# PROK_drum_F.net
KiCad netlist of a schematic drawn in EAGLE
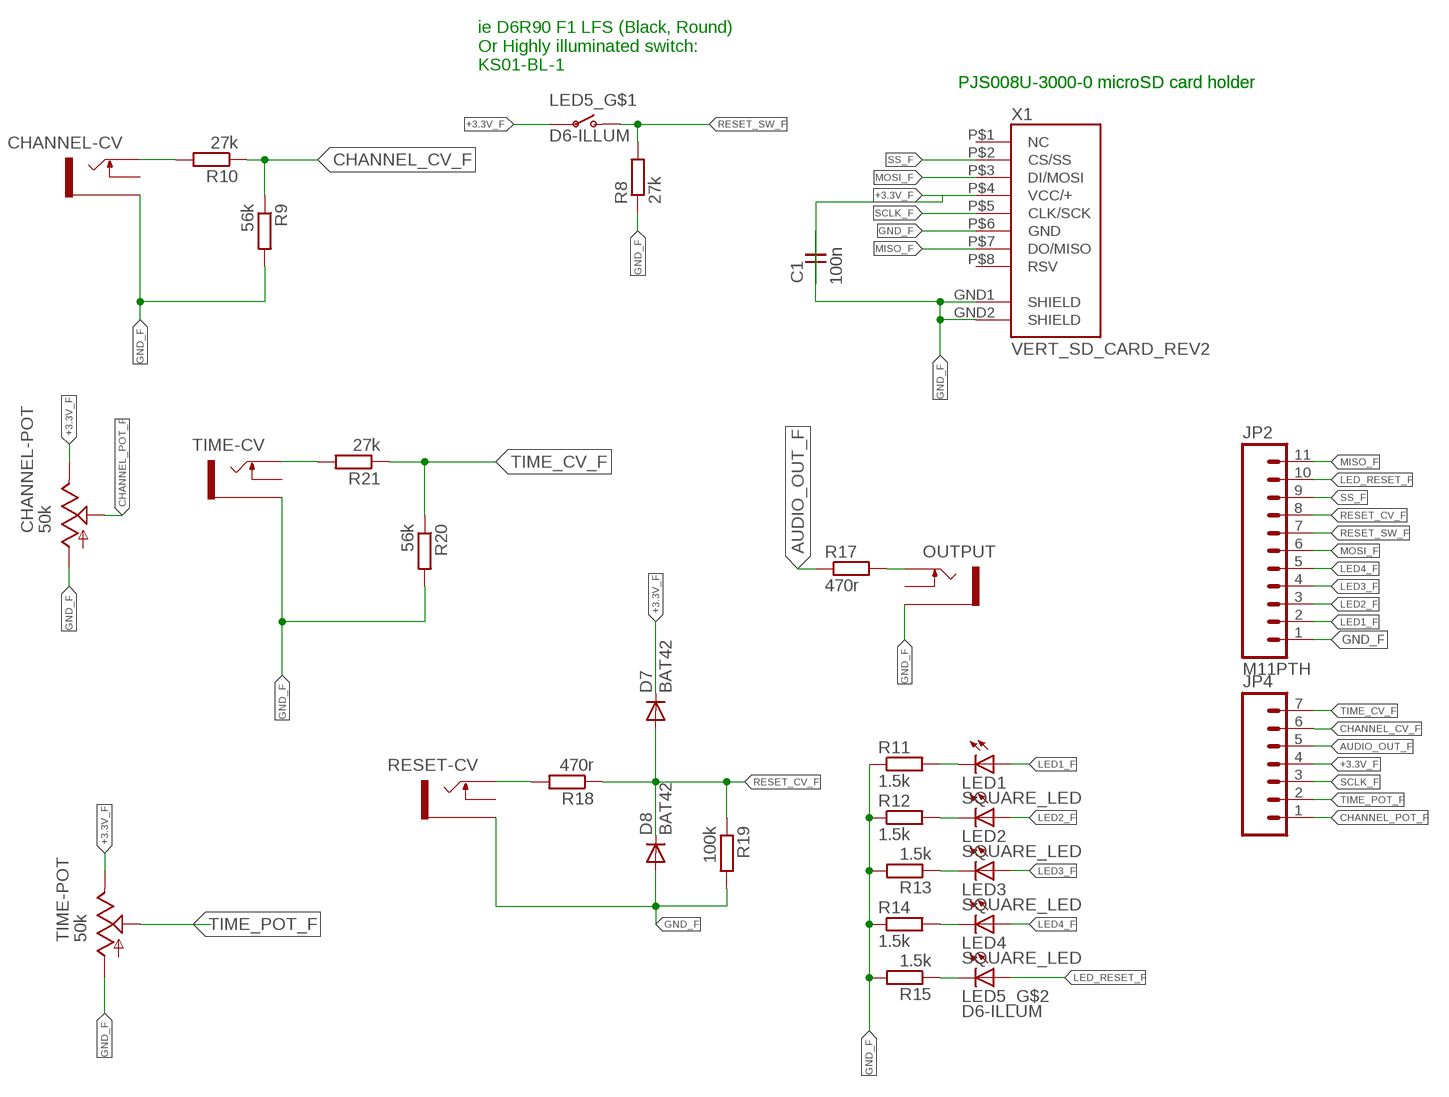
[diagram p0: schematic, sheet 1]

(export (version "E")
  (design (tool "Eeschema 10.0.6"))
  (components
    (comp (ref "C1")
      (value "100n")
      (footprint "eagle-import:C050-024X044")
      (libsource (lib "eagle-import") (part "C-EU050-024X044"))
    )
    (comp (ref "CHANNEL-CV")
      (value "THONKICONNNEW")
      (footprint "eagle-import:WQP-PJ301M-12_JACK")
      (libsource (lib "eagle-import") (part "THONKICONNNEW"))
    )
    (comp (ref "CHANNEL-POT")
      (value "50k")
      (footprint "eagle-import:EVUF")
      (libsource (lib "eagle-import") (part "ALPHA-9MMAF2"))
    )
    (comp (ref "D7")
      (value "BAT42")
      (footprint "eagle-import:DO34-7")
      (libsource (lib "eagle-import") (part "BAT42"))
    )
    (comp (ref "D8")
      (value "BAT42")
      (footprint "eagle-import:DO34-7")
      (libsource (lib "eagle-import") (part "BAT42"))
    )
    (comp (ref "JP2")
      (value "M11PTH")
      (footprint "eagle-import:1X11")
      (libsource (lib "eagle-import") (part "M11PTH"))
    )
    (comp (ref "JP4")
      (value "M07")
      (footprint "eagle-import:1X07")
      (libsource (lib "eagle-import") (part "M07"))
    )
    (comp (ref "LED1")
      (value "SQUARE_LED")
      (footprint "eagle-import:SQUARE_LED")
      (libsource (lib "eagle-import") (part "SQUARE_LED"))
    )
    (comp (ref "LED2")
      (value "SQUARE_LED")
      (footprint "eagle-import:SQUARE_LED")
      (libsource (lib "eagle-import") (part "SQUARE_LED"))
    )
    (comp (ref "LED3")
      (value "SQUARE_LED")
      (footprint "eagle-import:SQUARE_LED")
      (libsource (lib "eagle-import") (part "SQUARE_LED"))
    )
    (comp (ref "LED4")
      (value "SQUARE_LED")
      (footprint "eagle-import:SQUARE_LED")
      (libsource (lib "eagle-import") (part "SQUARE_LED"))
    )
    (comp (ref "LED5_")
      (value "D6-ILLUM")
      (footprint "eagle-import:D6_PUSH_SWITCH_ILLUM")
      (libsource (lib "eagle-import") (part "D6-ILLUM"))
    )
    (comp (ref "OUTPUT")
      (value "THONKICONNNEW")
      (footprint "eagle-import:WQP-PJ301M-12_JACK")
      (libsource (lib "eagle-import") (part "THONKICONNNEW"))
    )
    (comp (ref "R8")
      (value "27k")
      (footprint "eagle-import:7MM_RESISTOR")
      (libsource (lib "eagle-import") (part "RESISTOR7MM"))
    )
    (comp (ref "R9")
      (value "56k")
      (footprint "eagle-import:7MM_RESISTOR")
      (libsource (lib "eagle-import") (part "RESISTOR7MM"))
    )
    (comp (ref "R10")
      (value "27k")
      (footprint "eagle-import:VERTICAL_RESISTOR")
      (libsource (lib "eagle-import") (part "RESISTORVERTICAL"))
    )
    (comp (ref "R11")
      (value "1.5k")
      (footprint "eagle-import:7MM_RESISTOR")
      (libsource (lib "eagle-import") (part "RESISTOR7MM"))
    )
    (comp (ref "R12")
      (value "1.5k")
      (footprint "eagle-import:7MM_RESISTOR")
      (libsource (lib "eagle-import") (part "RESISTOR7MM"))
    )
    (comp (ref "R13")
      (value "1.5k")
      (footprint "eagle-import:VERTICAL_RESISTOR")
      (libsource (lib "eagle-import") (part "RESISTORVERTICAL"))
    )
    (comp (ref "R14")
      (value "1.5k")
      (footprint "eagle-import:7MM_RESISTOR")
      (libsource (lib "eagle-import") (part "RESISTOR7MM"))
    )
    (comp (ref "R15")
      (value "1.5k")
      (footprint "eagle-import:7MM_RESISTOR")
      (libsource (lib "eagle-import") (part "RESISTOR7MM"))
    )
    (comp (ref "R17")
      (value "470r")
      (footprint "eagle-import:7MM_RESISTOR")
      (libsource (lib "eagle-import") (part "RESISTOR7MM"))
    )
    (comp (ref "R18")
      (value "470r")
      (footprint "eagle-import:7MM_RESISTOR")
      (libsource (lib "eagle-import") (part "RESISTOR7MM"))
    )
    (comp (ref "R19")
      (value "100k")
      (footprint "eagle-import:7MM_RESISTOR")
      (libsource (lib "eagle-import") (part "RESISTOR7MM"))
    )
    (comp (ref "R20")
      (value "56k")
      (footprint "eagle-import:VERTICAL_RESISTOR")
      (libsource (lib "eagle-import") (part "RESISTORVERTICAL"))
    )
    (comp (ref "R21")
      (value "27k")
      (footprint "eagle-import:VERTICAL_RESISTOR")
      (libsource (lib "eagle-import") (part "RESISTORVERTICAL"))
    )
    (comp (ref "RESET-CV")
      (value "THONKICONNNEW")
      (footprint "eagle-import:WQP-PJ301M-12_JACK")
      (libsource (lib "eagle-import") (part "THONKICONNNEW"))
    )
    (comp (ref "TIME-CV")
      (value "THONKICONNNEW")
      (footprint "eagle-import:WQP-PJ301M-12_JACK")
      (libsource (lib "eagle-import") (part "THONKICONNNEW"))
    )
    (comp (ref "TIME-POT")
      (value "50k")
      (footprint "eagle-import:EVUF")
      (libsource (lib "eagle-import") (part "ALPHA-9MMAF2"))
    )
    (comp (ref "X1")
      (value "VERT_SD_CARD_REV2")
      (footprint "eagle-import:VERT_MICROSD_REV2")
      (libsource (lib "eagle-import") (part "VERT_SD_CARD_REV2"))
    )
  )
  (nets
    (net (code "1") (name "+3.3V_F") (class "Default")
      (node (ref "C1") (pin "2") (pinfunction "2_2") (pintype "passive"))
      (node (ref "CHANNEL-POT") (pin "3") (pinfunction "E_3") (pintype "passive"))
      (node (ref "D7") (pin "C") (pinfunction "C_C") (pintype "passive"))
      (node (ref "JP4") (pin "4") (pinfunction "4_4") (pintype "passive"))
      (node (ref "LED5_") (pin "P$3") (pinfunction "P_P$3") (pintype "passive"))
      (node (ref "LED5_") (pin "P$4") (pinfunction "P_P$4") (pintype "passive"))
      (node (ref "TIME-POT") (pin "3") (pinfunction "E_3") (pintype "passive"))
      (node (ref "X1") (pin "P$4") (pinfunction "VCC/+_P$4") (pintype "bidirectional"))
    )
    (net (code "2") (name "AUDIO_OUT_F") (class "Default")
      (node (ref "JP4") (pin "5") (pinfunction "5_5") (pintype "passive"))
      (node (ref "R17") (pin "1") (pinfunction "1_1") (pintype "passive"))
    )
    (net (code "3") (name "CHANNEL_CV_F") (class "Default")
      (node (ref "JP4") (pin "6") (pinfunction "6_6") (pintype "passive"))
      (node (ref "R10") (pin "1") (pinfunction "1_1") (pintype "passive"))
      (node (ref "R9") (pin "1") (pinfunction "1_1") (pintype "passive"))
    )
    (net (code "4") (name "CHANNEL_POT_F") (class "Default")
      (node (ref "CHANNEL-POT") (pin "2") (pinfunction "S_2") (pintype "passive"))
      (node (ref "JP4") (pin "1") (pinfunction "1_1") (pintype "passive"))
    )
    (net (code "5") (name "GND_F") (class "Default")
      (node (ref "C1") (pin "1") (pinfunction "1_1") (pintype "passive"))
      (node (ref "CHANNEL-CV") (pin "P$3_SLEEVE") (pinfunction "SLEEVE_P$3_SLEEVE") (pintype "passive"))
      (node (ref "CHANNEL-POT") (pin "1") (pinfunction "A_1") (pintype "passive"))
      (node (ref "D8") (pin "A") (pinfunction "A_A") (pintype "passive"))
      (node (ref "JP2") (pin "1") (pinfunction "1_1") (pintype "passive"))
      (node (ref "OUTPUT") (pin "P$3_SLEEVE") (pinfunction "SLEEVE_P$3_SLEEVE") (pintype "passive"))
      (node (ref "R11") (pin "1") (pinfunction "1_1") (pintype "passive"))
      (node (ref "R12") (pin "1") (pinfunction "1_1") (pintype "passive"))
      (node (ref "R13") (pin "2") (pinfunction "2_2") (pintype "passive"))
      (node (ref "R14") (pin "1") (pinfunction "1_1") (pintype "passive"))
      (node (ref "R15") (pin "2") (pinfunction "2_2") (pintype "passive"))
      (node (ref "R19") (pin "2") (pinfunction "2_2") (pintype "passive"))
      (node (ref "R20") (pin "2") (pinfunction "2_2") (pintype "passive"))
      (node (ref "R8") (pin "1") (pinfunction "1_1") (pintype "passive"))
      (node (ref "R9") (pin "2") (pinfunction "2_2") (pintype "passive"))
      (node (ref "RESET-CV") (pin "P$3_SLEEVE") (pinfunction "SLEEVE_P$3_SLEEVE") (pintype "passive"))
      (node (ref "TIME-CV") (pin "P$3_SLEEVE") (pinfunction "SLEEVE_P$3_SLEEVE") (pintype "passive"))
      (node (ref "TIME-POT") (pin "1") (pinfunction "A_1") (pintype "passive"))
      (node (ref "X1") (pin "GND1") (pinfunction "SHIELD_GND1") (pintype "bidirectional"))
      (node (ref "X1") (pin "GND2") (pinfunction "SHIELD_GND2") (pintype "bidirectional"))
      (node (ref "X1") (pin "P$6") (pinfunction "GND_P$6") (pintype "bidirectional"))
    )
    (net (code "6") (name "LED1_F") (class "Default")
      (node (ref "JP2") (pin "2") (pinfunction "2_2") (pintype "passive"))
      (node (ref "LED1") (pin "ANODE") (pinfunction "A_ANODE") (pintype "passive"))
    )
    (net (code "7") (name "LED2_F") (class "Default")
      (node (ref "JP2") (pin "3") (pinfunction "3_3") (pintype "passive"))
      (node (ref "LED2") (pin "ANODE") (pinfunction "A_ANODE") (pintype "passive"))
    )
    (net (code "8") (name "LED3_F") (class "Default")
      (node (ref "JP2") (pin "4") (pinfunction "4_4") (pintype "passive"))
      (node (ref "LED3") (pin "ANODE") (pinfunction "A_ANODE") (pintype "passive"))
    )
    (net (code "9") (name "LED4_F") (class "Default")
      (node (ref "JP2") (pin "5") (pinfunction "5_5") (pintype "passive"))
      (node (ref "LED4") (pin "ANODE") (pinfunction "A_ANODE") (pintype "passive"))
    )
    (net (code "10") (name "LED_RESET_F") (class "Default")
      (node (ref "JP2") (pin "10") (pinfunction "10_10") (pintype "passive"))
      (node (ref "LED5_") (pin "LED+") (pinfunction "A_LED+") (pintype "passive"))
    )
    (net (code "11") (name "MISO_F") (class "Default")
      (node (ref "JP2") (pin "11") (pinfunction "11_11") (pintype "passive"))
      (node (ref "X1") (pin "P$7") (pinfunction "DO/MISO_P$7") (pintype "bidirectional"))
    )
    (net (code "12") (name "MOSI_F") (class "Default")
      (node (ref "JP2") (pin "6") (pinfunction "6_6") (pintype "passive"))
      (node (ref "X1") (pin "P$3") (pinfunction "DI/MOSI_P$3") (pintype "bidirectional"))
    )
    (net (code "13") (name "Net-(CHANNEL-CV-TIP)") (class "Default")
      (node (ref "CHANNEL-CV") (pin "P$1_TIP") (pinfunction "TIP_P$1_TIP") (pintype "passive"))
      (node (ref "R10") (pin "2") (pinfunction "2_2") (pintype "passive"))
    )
    (net (code "14") (name "Net-(LED1-C)") (class "Default")
      (node (ref "LED1") (pin "CATHODE") (pinfunction "C_CATHODE") (pintype "passive"))
      (node (ref "R11") (pin "2") (pinfunction "2_2") (pintype "passive"))
    )
    (net (code "15") (name "Net-(LED2-C)") (class "Default")
      (node (ref "LED2") (pin "CATHODE") (pinfunction "C_CATHODE") (pintype "passive"))
      (node (ref "R12") (pin "2") (pinfunction "2_2") (pintype "passive"))
    )
    (net (code "16") (name "Net-(LED3-C)") (class "Default")
      (node (ref "LED3") (pin "CATHODE") (pinfunction "C_CATHODE") (pintype "passive"))
      (node (ref "R13") (pin "1") (pinfunction "1_1") (pintype "passive"))
    )
    (net (code "17") (name "Net-(LED4-C)") (class "Default")
      (node (ref "LED4") (pin "CATHODE") (pinfunction "C_CATHODE") (pintype "passive"))
      (node (ref "R14") (pin "2") (pinfunction "2_2") (pintype "passive"))
    )
    (net (code "18") (name "Net-(LED5_B-C)") (class "Default")
      (node (ref "LED5_") (pin "LED-") (pinfunction "C_LED-") (pintype "passive"))
      (node (ref "R15") (pin "1") (pinfunction "1_1") (pintype "passive"))
    )
    (net (code "19") (name "Net-(OUTPUT-TIP)") (class "Default")
      (node (ref "OUTPUT") (pin "P$1_TIP") (pinfunction "TIP_P$1_TIP") (pintype "passive"))
      (node (ref "R17") (pin "2") (pinfunction "2_2") (pintype "passive"))
    )
    (net (code "20") (name "Net-(RESET-CV-TIP)") (class "Default")
      (node (ref "R18") (pin "2") (pinfunction "2_2") (pintype "passive"))
      (node (ref "RESET-CV") (pin "P$1_TIP") (pinfunction "TIP_P$1_TIP") (pintype "passive"))
    )
    (net (code "21") (name "Net-(TIME-CV-TIP)") (class "Default")
      (node (ref "R21") (pin "2") (pinfunction "2_2") (pintype "passive"))
      (node (ref "TIME-CV") (pin "P$1_TIP") (pinfunction "TIP_P$1_TIP") (pintype "passive"))
    )
    (net (code "22") (name "RESET_CV_F") (class "Default")
      (node (ref "D7") (pin "A") (pinfunction "A_A") (pintype "passive"))
      (node (ref "D8") (pin "C") (pinfunction "C_C") (pintype "passive"))
      (node (ref "JP2") (pin "8") (pinfunction "8_8") (pintype "passive"))
      (node (ref "R18") (pin "1") (pinfunction "1_1") (pintype "passive"))
      (node (ref "R19") (pin "1") (pinfunction "1_1") (pintype "passive"))
    )
    (net (code "23") (name "RESET_SW_F") (class "Default")
      (node (ref "JP2") (pin "7") (pinfunction "7_7") (pintype "passive"))
      (node (ref "LED5_") (pin "P$1") (pinfunction "O_P$1") (pintype "passive"))
      (node (ref "LED5_") (pin "P$2") (pinfunction "O_P$2") (pintype "passive"))
      (node (ref "R8") (pin "2") (pinfunction "2_2") (pintype "passive"))
    )
    (net (code "24") (name "SCLK_F") (class "Default")
      (node (ref "JP4") (pin "3") (pinfunction "3_3") (pintype "passive"))
      (node (ref "X1") (pin "P$5") (pinfunction "CLK/SCK_P$5") (pintype "bidirectional"))
    )
    (net (code "25") (name "SS_F") (class "Default")
      (node (ref "JP2") (pin "9") (pinfunction "9_9") (pintype "passive"))
      (node (ref "X1") (pin "P$2") (pinfunction "CS/SS_P$2") (pintype "bidirectional"))
    )
    (net (code "26") (name "TIME_CV_F") (class "Default")
      (node (ref "JP4") (pin "7") (pinfunction "7_7") (pintype "passive"))
      (node (ref "R20") (pin "1") (pinfunction "1_1") (pintype "passive"))
      (node (ref "R21") (pin "1") (pinfunction "1_1") (pintype "passive"))
    )
    (net (code "27") (name "TIME_POT_F") (class "Default")
      (node (ref "JP4") (pin "2") (pinfunction "2_2") (pintype "passive"))
      (node (ref "TIME-POT") (pin "2") (pinfunction "S_2") (pintype "passive"))
    )
    (net (code "28") (name "unconnected-(CHANNEL-CV-SWITCH-PadP$2_SWITCH)") (class "Default")
      (node (ref "CHANNEL-CV") (pin "P$2_SWITCH") (pinfunction "SWITCH_P$2_SWITCH") (pintype "passive"))
    )
    (net (code "29") (name "unconnected-(OUTPUT-SWITCH-PadP$2_SWITCH)") (class "Default")
      (node (ref "OUTPUT") (pin "P$2_SWITCH") (pinfunction "SWITCH_P$2_SWITCH") (pintype "passive"))
    )
    (net (code "30") (name "unconnected-(RESET-CV-SWITCH-PadP$2_SWITCH)") (class "Default")
      (node (ref "RESET-CV") (pin "P$2_SWITCH") (pinfunction "SWITCH_P$2_SWITCH") (pintype "passive"))
    )
    (net (code "31") (name "unconnected-(TIME-CV-SWITCH-PadP$2_SWITCH)") (class "Default")
      (node (ref "TIME-CV") (pin "P$2_SWITCH") (pinfunction "SWITCH_P$2_SWITCH") (pintype "passive"))
    )
    (net (code "32") (name "unconnected-(X1-NC-PadP$1)") (class "Default")
      (node (ref "X1") (pin "P$1") (pinfunction "NC_P$1") (pintype "bidirectional"))
    )
    (net (code "33") (name "unconnected-(X1-RSV-PadP$8)") (class "Default")
      (node (ref "X1") (pin "P$8") (pinfunction "RSV_P$8") (pintype "bidirectional"))
    )
  )
)
